# mach_slave.net
KiCad netlist of a schematic drawn in Altium Designer
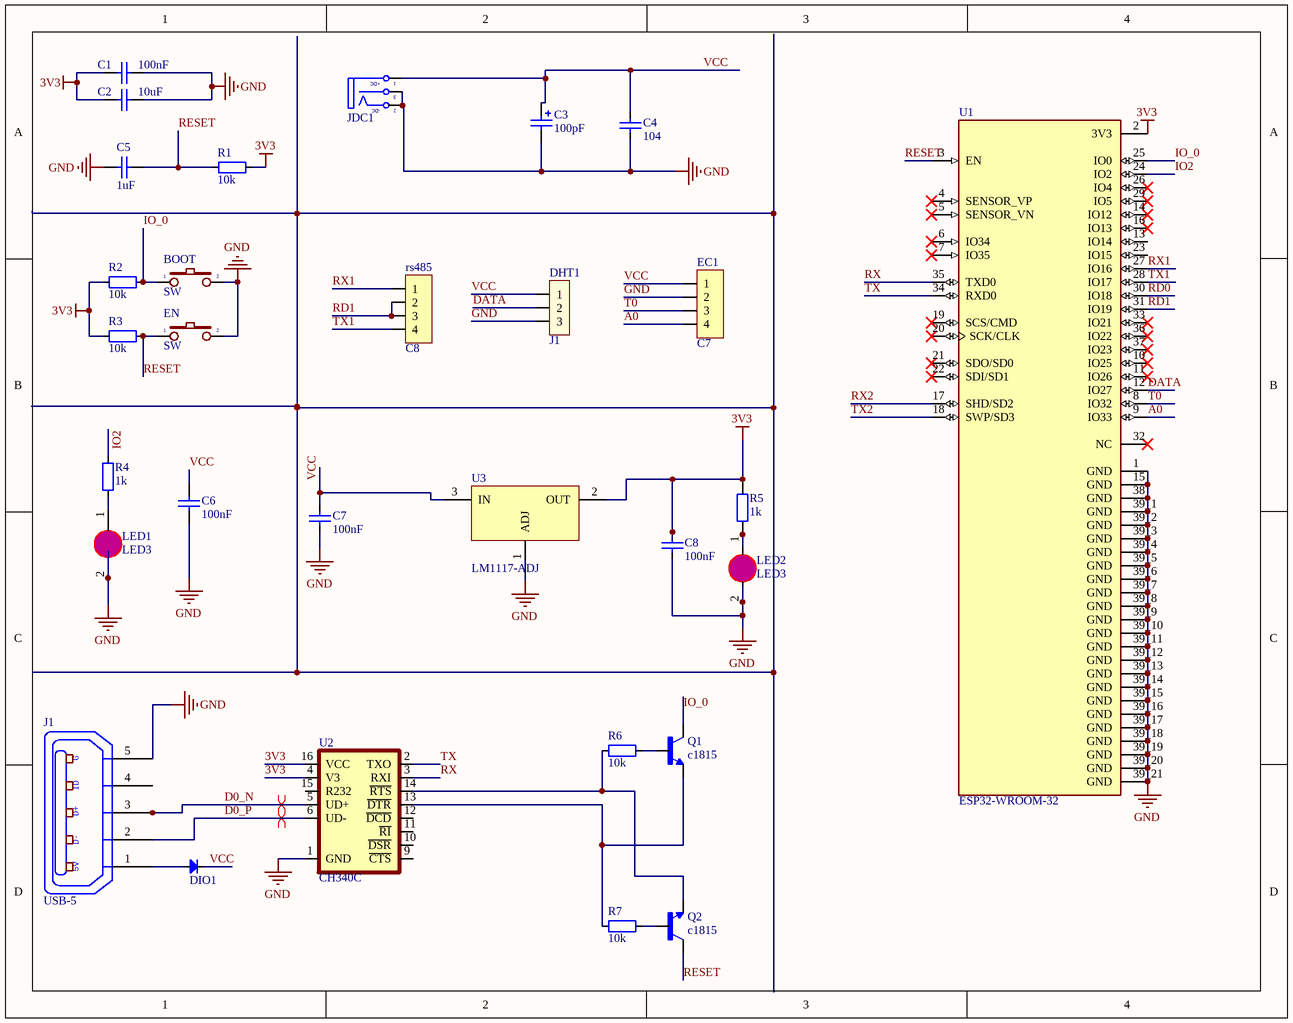
[diagram p0: mach slave.SchDoc]

(export (version "E")
  (design (tool "Eeschema 10.0.6"))
  (components
    (comp (ref "BOOT")
      (value "SW")
      (footprint "SW-SMD")
      (description "Switch button 2 pin")
      (libsource (lib "My Library") (part "SW2"))
    )
    (comp (ref "C1")
      (value "100nF")
      (footprint "CAP_0805")
      (description "Capacitor")
      (fields (field (name "PUBLISHER") "Altium Limited"))
      (libsource (lib "") (part "CapSMD_1"))
    )
    (comp (ref "C2")
      (value "10uF")
      (footprint "CAP_0805")
      (description "Capacitor")
      (fields (field (name "PUBLISHER") "Altium Limited"))
      (libsource (lib "") (part "CapSMD_1"))
    )
    (comp (ref "C3")
      (value "100pF")
      (footprint "CAP-ALU-SMD-C")
      (description "Polarized Capacitor (Radial)")
      (fields (field (name "Comment") "Cap Pol SMD"))
      (libsource (lib "thuvienhoang") (part "Cap Pol SMD"))
    )
    (comp (ref "C4")
      (value "104")
      (footprint "CAP_0805")
      (description "Capacitor")
      (fields (field (name "PUBLISHER") "Altium Limited"))
      (libsource (lib "My Library") (part "CapSMD"))
    )
    (comp (ref "C5")
      (value "1uF")
      (footprint "CAP_0805")
      (description "Capacitor")
      (fields (field (name "PUBLISHER") "Altium Limited"))
      (libsource (lib "") (part "CapSMD_1"))
    )
    (comp (ref "C6")
      (value "100nF")
      (footprint "CAP_0805")
      (description "Capacitor")
      (fields (field (name "PUBLISHER") "Altium Limited"))
      (libsource (lib "") (part "CapSMD_1"))
    )
    (comp (ref "C7")
      (value "100nF")
      (footprint "CAP_0805")
      (description "Capacitor")
      (fields (field (name "PUBLISHER") "Altium Limited"))
      (libsource (lib "My Library") (part "CapSMD"))
    )
    (comp (ref "C8")
      (value "100nF")
      (footprint "CAP_0805")
      (description "Capacitor")
      (fields (field (name "PUBLISHER") "Altium Limited"))
      (libsource (lib "My Library") (part "CapSMD"))
    )
    (comp (ref "DHT1")
      (value "J1")
      (footprint "JP3")
      (description "Jumper 3")
      (libsource (lib "My Library") (part "JP3"))
    )
    (comp (ref "DIO1")
      (value "Diode SMD")
      (footprint "DIO-SMD-106")
      (description "Default Diode")
      (fields (field (name "PUBLISHER") "Altium Limited"))
      (libsource (lib "My Library 2") (part "Diode SMD"))
    )
    (comp (ref "EC1")
      (value "C7")
      (footprint "JP4-C1T")
      (description "WR-PHD 2.54 mm Angled Socket Header")
      (fields
        (field (name "MANUFACTURER") "Würth Elektronik eiSos GmbH")
        (field (name "PARTNO") "613004143121")
        (field (name "CREATED BY") "Karrer Zheng")
      )
      (libsource (lib "My Library") (part "JP4"))
    )
    (comp (ref "EN")
      (value "SW")
      (footprint "SW-SMD")
      (description "Switch button 2 pin")
      (libsource (lib "My Library") (part "SW2"))
    )
    (comp (ref "J1")
      (value "USB-5")
      (footprint "USB-M1")
      (fields
        (field (name "MANUFACTURER") "FCI")
        (field (name "MANUFACTURER PART NUMBER") "10118193-0001LF")
        (field (name ".CREATOR") "MM")
        (field (name ".CHECKED PCB") "RF")
        (field (name ".CHECKED SCH") "MM")
      )
      (libsource (lib "My Library 2") (part "USB-5"))
    )
    (comp (ref "JDC1")
      (value "Jack DC")
      (footprint "DC-IN")
      (description "Jack DC input")
      (libsource (lib "thuvienhoang") (part "Jack DC"))
    )
    (comp (ref "LED1")
      (value "LED3")
      (footprint "LED0805")
      (description "LED SMD 0805")
      (libsource (lib "My Library 2") (part "LED0805"))
    )
    (comp (ref "LED2")
      (value "LED3")
      (footprint "LED0805")
      (description "LED SMD 0805")
      (libsource (lib "My Library 2") (part "LED0805"))
    )
    (comp (ref "Q1")
      (value "c1815")
      (footprint "SOT95P240X97-3N")
      (description "Bipolar (BJT) Transistor NPN 45V 500mA 100MHz 250mW Surface Mount TO-236AB")
      (fields (field (name "MP") "BC817") (field (name "MF") "Rectron"))
      (libsource (lib "") (part "BC817_1"))
    )
    (comp (ref "Q2")
      (value "c1815")
      (footprint "SOT95P240X97-3N")
      (description "Bipolar (BJT) Transistor NPN 45V 500mA 100MHz 250mW Surface Mount TO-236AB")
      (fields (field (name "MP") "BC817") (field (name "MF") "Rectron"))
      (libsource (lib "BC817") (part "BC817"))
    )
    (comp (ref "R1")
      (value "10k")
      (footprint "RES-SMD-0805")
      (description "Resistor")
      (fields
        (field (name "MANUFACTURER") "Generic Components")
        (field (name "PUBLISHER") "Altium Hobart Technology Centre")
      )
      (libsource (lib "My Library") (part "Resistor - SMD"))
    )
    (comp (ref "R2")
      (value "10k")
      (footprint "RES-SMD-0805")
      (description "Resistor")
      (fields
        (field (name "MANUFACTURER") "Generic Components")
        (field (name "PUBLISHER") "Altium Hobart Technology Centre")
      )
      (libsource (lib "My Library") (part "Resistor - SMD"))
    )
    (comp (ref "R3")
      (value "10k")
      (footprint "RES-SMD-0805")
      (description "Resistor")
      (fields
        (field (name "MANUFACTURER") "Generic Components")
        (field (name "PUBLISHER") "Altium Hobart Technology Centre")
      )
      (libsource (lib "My Library") (part "Resistor - SMD"))
    )
    (comp (ref "R4")
      (value "1k")
      (footprint "RES-SMD-0805")
      (description "Resistor")
      (fields
        (field (name "MANUFACTURER") "Generic Components")
        (field (name "PUBLISHER") "Altium Hobart Technology Centre")
      )
      (libsource (lib "My Library") (part "Resistor - SMD"))
    )
    (comp (ref "R5")
      (value "1k")
      (footprint "RES-SMD-0805")
      (description "22")
      (fields
        (field (name "MANUFACTURER") "Generic Components")
        (field (name "PUBLISHER") "Altium Hobart Technology Centre")
      )
      (libsource (lib "") (part "Resistor - SMD_1"))
    )
    (comp (ref "R6")
      (value "10k")
      (footprint "RES-SMD-0603")
      (description "Resistor")
      (fields
        (field (name "MANUFACTURER") "Generic Components")
        (field (name "PUBLISHER") "Altium Hobart Technology Centre")
      )
      (libsource (lib "My Library") (part "Resistor - SMD"))
    )
    (comp (ref "R7")
      (value "10k")
      (footprint "RES-SMD-0603")
      (description "Resistor")
      (fields
        (field (name "MANUFACTURER") "Generic Components")
        (field (name "PUBLISHER") "Altium Hobart Technology Centre")
      )
      (libsource (lib "My Library") (part "Resistor - SMD"))
    )
    (comp (ref "rs485")
      (value "C8")
      (footprint "JP4-C1T")
      (description "WR-PHD 2.54 mm Angled Socket Header")
      (fields
        (field (name "MANUFACTURER") "Würth Elektronik eiSos GmbH")
        (field (name "PARTNO") "613004143121")
        (field (name "CREATED BY") "Karrer Zheng")
      )
      (libsource (lib "My Library") (part "JP4"))
    )
    (comp (ref "U1")
      (value "ESP32-WROOM-32")
      (footprint "MODULE_ESP32-WROOM-32")
      (fields (field (name "MF") "Espressif Systems"))
      (libsource (lib "ESP32-WROOM-32") (part "ESP32-WROOM-32"))
    )
    (comp (ref "U2")
      (value "CH340C")
      (footprint "SOP-16")
      (description "USB to serial chip CH340")
      (fields (field (name "MF") "WCH"))
      (libsource (lib "My Library") (part "CH340C"))
    )
    (comp (ref "U3")
      (value "LM1117-ADJ")
      (footprint "LM1117-SOP")
      (description "800mA Low-Dropout Linear Regulator")
      (fields (field (name "CREATOR") "Nguyen Ba Bien"))
      (libsource (lib "My Library 2") (part "LM1117-ADJ"))
    )
  )
  (nets
    (net (code "1") (name "/A0") (class "Default")
      (node (ref "EC1") (pin "4") (pinfunction "4_4") (pintype "passive"))
      (node (ref "U1") (pin "9") (pinfunction "IO33_9") (pintype "bidirectional"))
    )
    (net (code "2") (name "/D0_N") (class "Default")
      (node (ref "J1") (pin "3") (pinfunction "P3_3") (pintype "passive"))
      (node (ref "U2") (pin "5") (pinfunction "UD+_5") (pintype "bidirectional"))
    )
    (net (code "3") (name "/D0_P") (class "Default")
      (node (ref "J1") (pin "2") (pinfunction "P2_2") (pintype "passive"))
      (node (ref "U2") (pin "6") (pinfunction "UD-_6") (pintype "bidirectional"))
    )
    (net (code "4") (name "/DATA") (class "Default")
      (node (ref "DHT1") (pin "2") (pinfunction "2_2") (pintype "passive"))
      (node (ref "U1") (pin "12") (pinfunction "IO27_12") (pintype "bidirectional"))
    )
    (net (code "5") (name "/IO2") (class "Default")
      (node (ref "R4") (pin "2") (pinfunction "2_2") (pintype "passive"))
      (node (ref "U1") (pin "24") (pinfunction "IO2_24") (pintype "bidirectional"))
    )
    (net (code "6") (name "/IO_0") (class "Default")
      (node (ref "BOOT") (pin "1") (pinfunction "1_1") (pintype "passive"))
      (node (ref "Q1") (pin "3") (pinfunction "C_3") (pintype "passive"))
      (node (ref "R2") (pin "1") (pinfunction "1_1") (pintype "passive"))
      (node (ref "U1") (pin "25") (pinfunction "IO0_25") (pintype "bidirectional"))
    )
    (net (code "7") (name "/RD0") (class "Default")
      (node (ref "U1") (pin "30") (pinfunction "IO18_30") (pintype "bidirectional"))
    )
    (net (code "8") (name "/RD1") (class "Default")
      (node (ref "U1") (pin "31") (pinfunction "IO19_31") (pintype "bidirectional"))
      (node (ref "rs485") (pin "2") (pinfunction "2_2") (pintype "passive"))
      (node (ref "rs485") (pin "3") (pinfunction "3_3") (pintype "passive"))
    )
    (net (code "9") (name "/RESET") (class "Default")
      (node (ref "C5") (pin "1") (pinfunction "1_1") (pintype "passive"))
      (node (ref "EN") (pin "1") (pinfunction "1_1") (pintype "passive"))
      (node (ref "Q2") (pin "3") (pinfunction "C_3") (pintype "passive"))
      (node (ref "R1") (pin "2") (pinfunction "2_2") (pintype "passive"))
      (node (ref "R3") (pin "1") (pinfunction "1_1") (pintype "passive"))
      (node (ref "U1") (pin "3") (pinfunction "EN_3") (pintype "input"))
    )
    (net (code "10") (name "/RX") (class "Default")
      (node (ref "U1") (pin "35") (pinfunction "TXD0_35") (pintype "bidirectional"))
      (node (ref "U2") (pin "3") (pinfunction "RXI_3") (pintype "bidirectional"))
    )
    (net (code "11") (name "/RX1") (class "Default")
      (node (ref "U1") (pin "27") (pinfunction "IO16_27") (pintype "bidirectional"))
      (node (ref "rs485") (pin "1") (pinfunction "1_1") (pintype "passive"))
    )
    (net (code "12") (name "/RX2") (class "Default")
      (node (ref "U1") (pin "17") (pinfunction "SHD/SD2_17") (pintype "bidirectional"))
    )
    (net (code "13") (name "/T0") (class "Default")
      (node (ref "EC1") (pin "3") (pinfunction "3_3") (pintype "passive"))
      (node (ref "U1") (pin "8") (pinfunction "IO32_8") (pintype "bidirectional"))
    )
    (net (code "14") (name "/TX") (class "Default")
      (node (ref "U1") (pin "34") (pinfunction "RXD0_34") (pintype "bidirectional"))
      (node (ref "U2") (pin "2") (pinfunction "TXO_2") (pintype "bidirectional"))
    )
    (net (code "15") (name "/TX1") (class "Default")
      (node (ref "U1") (pin "28") (pinfunction "IO17_28") (pintype "bidirectional"))
      (node (ref "rs485") (pin "4") (pinfunction "4_4") (pintype "passive"))
    )
    (net (code "16") (name "/TX2") (class "Default")
      (node (ref "U1") (pin "18") (pinfunction "SWP/SD3_18") (pintype "bidirectional"))
    )
    (net (code "17") (name "/VCC") (class "Default")
      (node (ref "C3") (pin "1") (pinfunction "1_1") (pintype "passive"))
      (node (ref "C4") (pin "2") (pinfunction "2_2") (pintype "passive"))
      (node (ref "C6") (pin "2") (pinfunction "2_2") (pintype "passive"))
      (node (ref "C7") (pin "2") (pinfunction "2_2") (pintype "passive"))
      (node (ref "DHT1") (pin "1") (pinfunction "1_1") (pintype "passive"))
      (node (ref "DIO1") (pin "2") (pinfunction "K_2") (pintype "passive"))
      (node (ref "EC1") (pin "1") (pinfunction "1_1") (pintype "passive"))
      (node (ref "JDC1") (pin "1") (pinfunction "T_1") (pintype "passive"))
      (node (ref "U3") (pin "3") (pinfunction "IN_3") (pintype "passive"))
    )
    (net (code "18") (name "3V3") (class "Default")
      (node (ref "C1") (pin "1") (pinfunction "1_1") (pintype "passive"))
      (node (ref "C2") (pin "1") (pinfunction "1_1") (pintype "passive"))
      (node (ref "C8") (pin "2") (pinfunction "2_2") (pintype "passive"))
      (node (ref "R1") (pin "1") (pinfunction "1_1") (pintype "passive"))
      (node (ref "R2") (pin "2") (pinfunction "2_2") (pintype "passive"))
      (node (ref "R3") (pin "2") (pinfunction "2_2") (pintype "passive"))
      (node (ref "R5") (pin "1") (pinfunction "1_1") (pintype "passive"))
      (node (ref "U1") (pin "2") (pinfunction "3V3_2") (pintype "power_in"))
      (node (ref "U2") (pin "16") (pinfunction "VCC_16") (pintype "bidirectional"))
      (node (ref "U2") (pin "4") (pinfunction "V3_4") (pintype "bidirectional"))
      (node (ref "U3") (pin "2") (pinfunction "OUT_2") (pintype "passive"))
    )
    (net (code "19") (name "GND") (class "Default")
      (node (ref "BOOT") (pin "2") (pinfunction "2_2") (pintype "passive"))
      (node (ref "C1") (pin "2") (pinfunction "2_2") (pintype "passive"))
      (node (ref "C2") (pin "2") (pinfunction "2_2") (pintype "passive"))
      (node (ref "C3") (pin "2") (pinfunction "2_2") (pintype "passive"))
      (node (ref "C4") (pin "1") (pinfunction "1_1") (pintype "passive"))
      (node (ref "C5") (pin "2") (pinfunction "2_2") (pintype "passive"))
      (node (ref "C6") (pin "1") (pinfunction "1_1") (pintype "passive"))
      (node (ref "C7") (pin "1") (pinfunction "1_1") (pintype "passive"))
      (node (ref "C8") (pin "1") (pinfunction "1_1") (pintype "passive"))
      (node (ref "DHT1") (pin "3") (pinfunction "3_3") (pintype "passive"))
      (node (ref "EC1") (pin "2") (pinfunction "2_2") (pintype "passive"))
      (node (ref "EN") (pin "2") (pinfunction "2_2") (pintype "passive"))
      (node (ref "J1") (pin "5") (pinfunction "P5_5") (pintype "passive"))
      (node (ref "JDC1") (pin "2") (pinfunction "TN_2") (pintype "passive"))
      (node (ref "JDC1") (pin "3") (pinfunction "S_3") (pintype "power_in"))
      (node (ref "LED1") (pin "2") (pinfunction "K_2") (pintype "passive"))
      (node (ref "LED2") (pin "2") (pinfunction "K_2") (pintype "passive"))
      (node (ref "U1") (pin "1") (pinfunction "GND_1") (pintype "power_in"))
      (node (ref "U1") (pin "15") (pinfunction "GND_15") (pintype "power_in"))
      (node (ref "U1") (pin "38") (pinfunction "GND_38") (pintype "power_in"))
      (node (ref "U1") (pin "39_1") (pinfunction "GND_39_1") (pintype "power_in"))
      (node (ref "U1") (pin "39_10") (pinfunction "GND_39_10") (pintype "power_in"))
      (node (ref "U1") (pin "39_11") (pinfunction "GND_39_11") (pintype "power_in"))
      (node (ref "U1") (pin "39_12") (pinfunction "GND_39_12") (pintype "power_in"))
      (node (ref "U1") (pin "39_13") (pinfunction "GND_39_13") (pintype "power_in"))
      (node (ref "U1") (pin "39_14") (pinfunction "GND_39_14") (pintype "power_in"))
      (node (ref "U1") (pin "39_15") (pinfunction "GND_39_15") (pintype "power_in"))
      (node (ref "U1") (pin "39_16") (pinfunction "GND_39_16") (pintype "power_in"))
      (node (ref "U1") (pin "39_17") (pinfunction "GND_39_17") (pintype "power_in"))
      (node (ref "U1") (pin "39_18") (pinfunction "GND_39_18") (pintype "power_in"))
      (node (ref "U1") (pin "39_19") (pinfunction "GND_39_19") (pintype "power_in"))
      (node (ref "U1") (pin "39_2") (pinfunction "GND_39_2") (pintype "power_in"))
      (node (ref "U1") (pin "39_20") (pinfunction "GND_39_20") (pintype "power_in"))
      (node (ref "U1") (pin "39_21") (pinfunction "GND_39_21") (pintype "power_in"))
      (node (ref "U1") (pin "39_3") (pinfunction "GND_39_3") (pintype "power_in"))
      (node (ref "U1") (pin "39_4") (pinfunction "GND_39_4") (pintype "power_in"))
      (node (ref "U1") (pin "39_5") (pinfunction "GND_39_5") (pintype "power_in"))
      (node (ref "U1") (pin "39_6") (pinfunction "GND_39_6") (pintype "power_in"))
      (node (ref "U1") (pin "39_7") (pinfunction "GND_39_7") (pintype "power_in"))
      (node (ref "U1") (pin "39_8") (pinfunction "GND_39_8") (pintype "power_in"))
      (node (ref "U1") (pin "39_9") (pinfunction "GND_39_9") (pintype "power_in"))
      (node (ref "U2") (pin "1") (pinfunction "GND_1") (pintype "bidirectional"))
      (node (ref "U3") (pin "1") (pinfunction "ADJ_1") (pintype "passive"))
    )
    (net (code "20") (name "Net-(DIO1-A)") (class "Default")
      (node (ref "DIO1") (pin "1") (pinfunction "A_1") (pintype "passive"))
      (node (ref "J1") (pin "1") (pinfunction "P1_1") (pintype "passive"))
    )
    (net (code "21") (name "Net-(LED1-A)") (class "Default")
      (node (ref "LED1") (pin "1") (pinfunction "A_1") (pintype "passive"))
      (node (ref "R4") (pin "1") (pinfunction "1_1") (pintype "passive"))
    )
    (net (code "22") (name "Net-(LED2-A)") (class "Default")
      (node (ref "LED2") (pin "1") (pinfunction "A_1") (pintype "passive"))
      (node (ref "R5") (pin "2") (pinfunction "2_2") (pintype "passive"))
    )
    (net (code "23") (name "Net-(Q1-B)") (class "Default")
      (node (ref "Q1") (pin "1") (pinfunction "B_1") (pintype "passive"))
      (node (ref "R6") (pin "1") (pinfunction "1_1") (pintype "passive"))
    )
    (net (code "24") (name "Net-(Q1-E)") (class "Default")
      (node (ref "Q1") (pin "2") (pinfunction "E_2") (pintype "passive"))
      (node (ref "R7") (pin "2") (pinfunction "2_2") (pintype "passive"))
      (node (ref "U2") (pin "13") (pinfunction "~{DTR}_13") (pintype "bidirectional"))
    )
    (net (code "25") (name "Net-(Q2-B)") (class "Default")
      (node (ref "Q2") (pin "1") (pinfunction "B_1") (pintype "passive"))
      (node (ref "R7") (pin "1") (pinfunction "1_1") (pintype "passive"))
    )
    (net (code "26") (name "Net-(Q2-E)") (class "Default")
      (node (ref "Q2") (pin "2") (pinfunction "E_2") (pintype "passive"))
      (node (ref "R6") (pin "2") (pinfunction "2_2") (pintype "passive"))
      (node (ref "U2") (pin "14") (pinfunction "~{RTS}_14") (pintype "bidirectional"))
    )
    (net (code "27") (name "unconnected-(J1-P4-Pad4)") (class "Default")
      (node (ref "J1") (pin "4") (pinfunction "P4_4") (pintype "passive"))
    )
    (net (code "28") (name "unconnected-(U1-IO4-Pad26)") (class "Default")
      (node (ref "U1") (pin "26") (pinfunction "IO4_26") (pintype "bidirectional+no_connect"))
    )
    (net (code "29") (name "unconnected-(U1-IO5-Pad29)") (class "Default")
      (node (ref "U1") (pin "29") (pinfunction "IO5_29") (pintype "bidirectional+no_connect"))
    )
    (net (code "30") (name "unconnected-(U1-IO12-Pad14)") (class "Default")
      (node (ref "U1") (pin "14") (pinfunction "IO12_14") (pintype "bidirectional+no_connect"))
    )
    (net (code "31") (name "unconnected-(U1-IO13-Pad16)") (class "Default")
      (node (ref "U1") (pin "16") (pinfunction "IO13_16") (pintype "bidirectional+no_connect"))
    )
    (net (code "32") (name "unconnected-(U1-IO14-Pad13)") (class "Default")
      (node (ref "U1") (pin "13") (pinfunction "IO14_13") (pintype "bidirectional"))
    )
    (net (code "33") (name "unconnected-(U1-IO15-Pad23)") (class "Default")
      (node (ref "U1") (pin "23") (pinfunction "IO15_23") (pintype "bidirectional"))
    )
    (net (code "34") (name "unconnected-(U1-IO21-Pad33)") (class "Default")
      (node (ref "U1") (pin "33") (pinfunction "IO21_33") (pintype "bidirectional+no_connect"))
    )
    (net (code "35") (name "unconnected-(U1-IO22-Pad36)") (class "Default")
      (node (ref "U1") (pin "36") (pinfunction "IO22_36") (pintype "bidirectional+no_connect"))
    )
    (net (code "36") (name "unconnected-(U1-IO23-Pad37)") (class "Default")
      (node (ref "U1") (pin "37") (pinfunction "IO23_37") (pintype "bidirectional+no_connect"))
    )
    (net (code "37") (name "unconnected-(U1-IO25-Pad10)") (class "Default")
      (node (ref "U1") (pin "10") (pinfunction "IO25_10") (pintype "bidirectional+no_connect"))
    )
    (net (code "38") (name "unconnected-(U1-IO26-Pad11)") (class "Default")
      (node (ref "U1") (pin "11") (pinfunction "IO26_11") (pintype "bidirectional+no_connect"))
    )
    (net (code "39") (name "unconnected-(U1-IO34-Pad6)") (class "Default")
      (node (ref "U1") (pin "6") (pinfunction "IO34_6") (pintype "input+no_connect"))
    )
    (net (code "40") (name "unconnected-(U1-IO35-Pad7)") (class "Default")
      (node (ref "U1") (pin "7") (pinfunction "IO35_7") (pintype "input+no_connect"))
    )
    (net (code "41") (name "unconnected-(U1-NC-Pad32)") (class "Default")
      (node (ref "U1") (pin "32") (pinfunction "NC_32") (pintype "passive+no_connect"))
    )
    (net (code "42") (name "unconnected-(U1-SCK{slash}CLK-Pad20)") (class "Default")
      (node (ref "U1") (pin "20") (pinfunction "SCK/CLK_20") (pintype "bidirectional+no_connect"))
    )
    (net (code "43") (name "unconnected-(U1-SCS{slash}CMD-Pad19)") (class "Default")
      (node (ref "U1") (pin "19") (pinfunction "SCS/CMD_19") (pintype "bidirectional+no_connect"))
    )
    (net (code "44") (name "unconnected-(U1-SDI{slash}SD1-Pad22)") (class "Default")
      (node (ref "U1") (pin "22") (pinfunction "SDI/SD1_22") (pintype "bidirectional+no_connect"))
    )
    (net (code "45") (name "unconnected-(U1-SDO{slash}SD0-Pad21)") (class "Default")
      (node (ref "U1") (pin "21") (pinfunction "SDO/SD0_21") (pintype "bidirectional+no_connect"))
    )
    (net (code "46") (name "unconnected-(U1-SENSOR_VN-Pad5)") (class "Default")
      (node (ref "U1") (pin "5") (pinfunction "SENSOR_VN_5") (pintype "input+no_connect"))
    )
    (net (code "47") (name "unconnected-(U1-SENSOR_VP-Pad4)") (class "Default")
      (node (ref "U1") (pin "4") (pinfunction "SENSOR_VP_4") (pintype "input+no_connect"))
    )
    (net (code "48") (name "unconnected-(U2-R232-Pad15)") (class "Default")
      (node (ref "U2") (pin "15") (pinfunction "R232_15") (pintype "bidirectional"))
    )
    (net (code "49") (name "unconnected-(U2-~{CTS}-Pad9)") (class "Default")
      (node (ref "U2") (pin "9") (pinfunction "~{CTS}_9") (pintype "bidirectional"))
    )
    (net (code "50") (name "unconnected-(U2-~{DCD}-Pad12)") (class "Default")
      (node (ref "U2") (pin "12") (pinfunction "~{DCD}_12") (pintype "bidirectional"))
    )
    (net (code "51") (name "unconnected-(U2-~{DSR}-Pad10)") (class "Default")
      (node (ref "U2") (pin "10") (pinfunction "~{DSR}_10") (pintype "bidirectional"))
    )
    (net (code "52") (name "unconnected-(U2-~{RI}-Pad11)") (class "Default")
      (node (ref "U2") (pin "11") (pinfunction "~{RI}_11") (pintype "bidirectional"))
    )
  )
)
